# Alarms_and_Buttons.net
KiCad netlist of a schematic drawn in Altium Designer
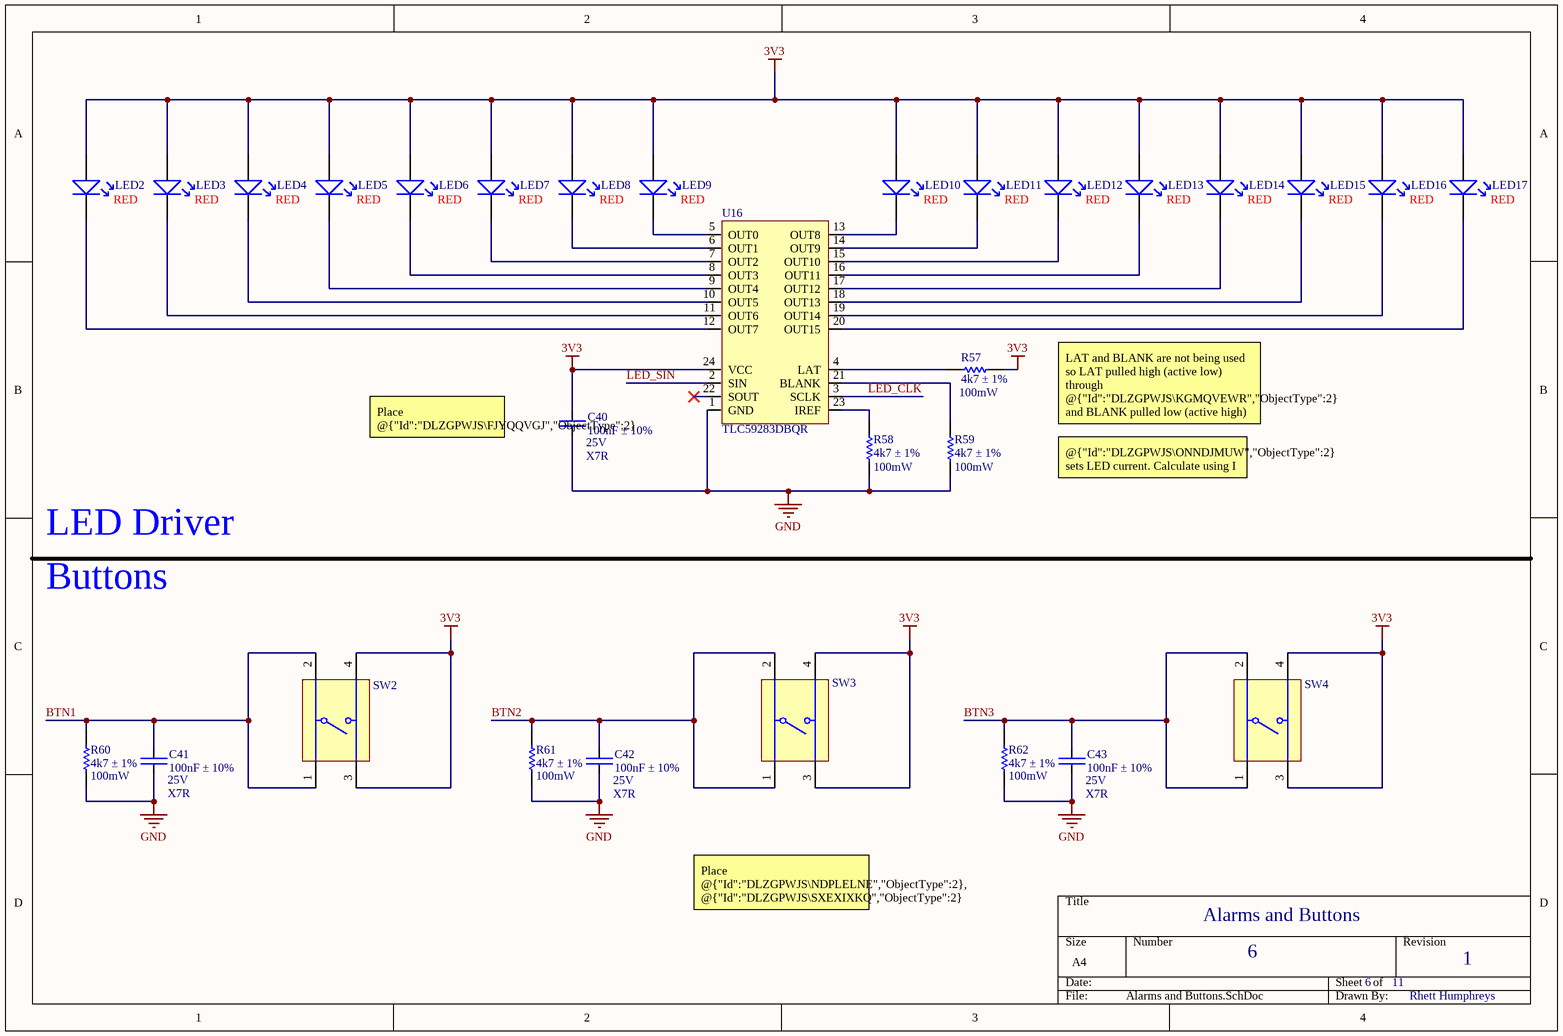
[diagram p0: Alarms and Buttons.SchDoc]

(export (version "E")
  (design (tool "Eeschema 10.0.6"))
  (components
    (comp (ref "C40")
      (value "100nF ± 10%")
      (footprint "CAP-0603")
      (description "Capacitor chip unpolarized. 0603")
      (libsource (lib "Master") (part "CAP-0603"))
    )
    (comp (ref "C41")
      (value "100nF ± 10%")
      (footprint "CAP-0603")
      (description "Capacitor chip unpolarized. 0603")
      (libsource (lib "Master") (part "CAP-0603"))
    )
    (comp (ref "C42")
      (value "100nF ± 10%")
      (footprint "CAP-0603")
      (description "Capacitor chip unpolarized. 0603")
      (libsource (lib "Master") (part "CAP-0603"))
    )
    (comp (ref "C43")
      (value "100nF ± 10%")
      (footprint "CAP-0603")
      (description "Capacitor chip unpolarized. 0603")
      (libsource (lib "Master") (part "CAP-0603"))
    )
    (comp (ref "LED2") (value "~") (footprint "0603 LED") (libsource (lib "Master") (part "0603 LED")))
    (comp (ref "LED3") (value "~") (footprint "0603 LED") (libsource (lib "Master") (part "0603 LED")))
    (comp (ref "LED4") (value "~") (footprint "0603 LED") (libsource (lib "Master") (part "0603 LED")))
    (comp (ref "LED5") (value "~") (footprint "0603 LED") (libsource (lib "Master") (part "0603 LED")))
    (comp (ref "LED6") (value "~") (footprint "0603 LED") (libsource (lib "Master") (part "0603 LED")))
    (comp (ref "LED7") (value "~") (footprint "0603 LED") (libsource (lib "Master") (part "0603 LED")))
    (comp (ref "LED8") (value "~") (footprint "0603 LED") (libsource (lib "Master") (part "0603 LED")))
    (comp (ref "LED9") (value "~") (footprint "0603 LED") (libsource (lib "Master") (part "0603 LED")))
    (comp (ref "LED10") (value "~") (footprint "0603 LED") (libsource (lib "Master") (part "0603 LED")))
    (comp (ref "LED11") (value "~") (footprint "0603 LED") (libsource (lib "Master") (part "0603 LED")))
    (comp (ref "LED12") (value "~") (footprint "0603 LED") (libsource (lib "Master") (part "0603 LED")))
    (comp (ref "LED13") (value "~") (footprint "0603 LED") (libsource (lib "Master") (part "0603 LED")))
    (comp (ref "LED14") (value "~") (footprint "0603 LED") (libsource (lib "Master") (part "0603 LED")))
    (comp (ref "LED15") (value "~") (footprint "0603 LED") (libsource (lib "Master") (part "0603 LED")))
    (comp (ref "LED16") (value "~") (footprint "0603 LED") (libsource (lib "Master") (part "0603 LED")))
    (comp (ref "LED17") (value "~") (footprint "0603 LED") (libsource (lib "Master") (part "0603 LED")))
    (comp (ref "R57")
      (value "4k7 ± 1%")
      (footprint "RES-0603")
      (description "Resistor chip. 0603")
      (libsource (lib "Master") (part "RES-0603"))
    )
    (comp (ref "R58")
      (value "4k7 ± 1%")
      (footprint "RES-0603")
      (description "Resistor chip. 0603")
      (libsource (lib "Master") (part "RES-0603"))
    )
    (comp (ref "R59")
      (value "4k7 ± 1%")
      (footprint "RES-0603")
      (description "Resistor chip. 0603")
      (libsource (lib "Master") (part "RES-0603"))
    )
    (comp (ref "R60")
      (value "4k7 ± 1%")
      (footprint "RES-0603")
      (description "Resistor chip. 0603")
      (libsource (lib "Master") (part "RES-0603"))
    )
    (comp (ref "R61")
      (value "4k7 ± 1%")
      (footprint "RES-0603")
      (description "Resistor chip. 0603")
      (libsource (lib "Master") (part "RES-0603"))
    )
    (comp (ref "R62")
      (value "4k7 ± 1%")
      (footprint "RES-0603")
      (description "Resistor chip. 0603")
      (libsource (lib "Master") (part "RES-0603"))
    )
    (comp (ref "SW2")
      (value "FSM4JSMATR")
      (footprint "TECO-FSM4JSMATR_V")
      (description "Micro Miniature Push Button Switch FSM JSM, 50 mA, -35 to 85 degC, 4-Pin SMD, RoHS, Tape and Reel")
      (fields (field (name "MANUFACTURER") "TE Connectivity"))
      (libsource (lib "Altium Content Vault") (part "SW-SPST-4_A"))
    )
    (comp (ref "SW3")
      (value "FSM4JSMATR")
      (footprint "TECO-FSM4JSMATR_V")
      (description "Micro Miniature Push Button Switch FSM JSM, 50 mA, -35 to 85 degC, 4-Pin SMD, RoHS, Tape and Reel")
      (fields (field (name "MANUFACTURER") "TE Connectivity"))
      (libsource (lib "Altium Content Vault") (part "SW-SPST-4_A"))
    )
    (comp (ref "SW4")
      (value "FSM4JSMATR")
      (footprint "TECO-FSM4JSMATR_V")
      (description "Micro Miniature Push Button Switch FSM JSM, 50 mA, -35 to 85 degC, 4-Pin SMD, RoHS, Tape and Reel")
      (fields (field (name "MANUFACTURER") "TE Connectivity"))
      (libsource (lib "Altium Content Vault") (part "SW-SPST-4_A"))
    )
    (comp (ref "U16")
      (value "TLC59283DBQR")
      (footprint "SOP64P600X175-24N")
      (description "LED Driver Const Current 16 Output")
      (libsource (lib "Master") (part "TLC59283DBQR"))
    )
  )
  (nets
    (net (code "1") (name "/BTN1") (class "Default")
      (node (ref "C41") (pin "2") (pintype "passive"))
      (node (ref "R60") (pin "1") (pintype "passive"))
      (node (ref "SW2") (pin "1") (pinfunction "1_1") (pintype "passive"))
      (node (ref "SW2") (pin "2") (pinfunction "2_2") (pintype "passive"))
    )
    (net (code "2") (name "/BTN2") (class "Default")
      (node (ref "C42") (pin "2") (pintype "passive"))
      (node (ref "R61") (pin "1") (pintype "passive"))
      (node (ref "SW3") (pin "1") (pinfunction "1_1") (pintype "passive"))
      (node (ref "SW3") (pin "2") (pinfunction "2_2") (pintype "passive"))
    )
    (net (code "3") (name "/BTN3") (class "Default")
      (node (ref "C43") (pin "2") (pintype "passive"))
      (node (ref "R62") (pin "1") (pintype "passive"))
      (node (ref "SW4") (pin "1") (pinfunction "1_1") (pintype "passive"))
      (node (ref "SW4") (pin "2") (pinfunction "2_2") (pintype "passive"))
    )
    (net (code "4") (name "/LED_CLK") (class "Default")
      (node (ref "U16") (pin "3") (pinfunction "SCLK_3") (pintype "passive"))
    )
    (net (code "5") (name "/LED_SIN") (class "Default")
      (node (ref "U16") (pin "2") (pinfunction "SIN_2") (pintype "passive"))
    )
    (net (code "6") (name "3V3") (class "Default")
      (node (ref "C40") (pin "2") (pintype "passive"))
      (node (ref "LED10") (pin "1") (pinfunction "6_1") (pintype "passive"))
      (node (ref "LED11") (pin "1") (pinfunction "6_1") (pintype "passive"))
      (node (ref "LED12") (pin "1") (pinfunction "6_1") (pintype "passive"))
      (node (ref "LED13") (pin "1") (pinfunction "6_1") (pintype "passive"))
      (node (ref "LED14") (pin "1") (pinfunction "6_1") (pintype "passive"))
      (node (ref "LED15") (pin "1") (pinfunction "6_1") (pintype "passive"))
      (node (ref "LED16") (pin "1") (pinfunction "6_1") (pintype "passive"))
      (node (ref "LED17") (pin "1") (pinfunction "6_1") (pintype "passive"))
      (node (ref "LED2") (pin "1") (pinfunction "6_1") (pintype "passive"))
      (node (ref "LED3") (pin "1") (pinfunction "6_1") (pintype "passive"))
      (node (ref "LED4") (pin "1") (pinfunction "6_1") (pintype "passive"))
      (node (ref "LED5") (pin "1") (pinfunction "6_1") (pintype "passive"))
      (node (ref "LED6") (pin "1") (pinfunction "6_1") (pintype "passive"))
      (node (ref "LED7") (pin "1") (pinfunction "6_1") (pintype "passive"))
      (node (ref "LED8") (pin "1") (pinfunction "6_1") (pintype "passive"))
      (node (ref "LED9") (pin "1") (pinfunction "6_1") (pintype "passive"))
      (node (ref "R57") (pin "2") (pintype "passive"))
      (node (ref "SW2") (pin "3") (pinfunction "3_3") (pintype "passive"))
      (node (ref "SW2") (pin "4") (pinfunction "4_4") (pintype "passive"))
      (node (ref "SW3") (pin "3") (pinfunction "3_3") (pintype "passive"))
      (node (ref "SW3") (pin "4") (pinfunction "4_4") (pintype "passive"))
      (node (ref "SW4") (pin "3") (pinfunction "3_3") (pintype "passive"))
      (node (ref "SW4") (pin "4") (pinfunction "4_4") (pintype "passive"))
      (node (ref "U16") (pin "24") (pinfunction "VCC_24") (pintype "passive"))
    )
    (net (code "7") (name "GND") (class "Default")
      (node (ref "C40") (pin "1") (pintype "passive"))
      (node (ref "C41") (pin "1") (pintype "passive"))
      (node (ref "C42") (pin "1") (pintype "passive"))
      (node (ref "C43") (pin "1") (pintype "passive"))
      (node (ref "R58") (pin "1") (pintype "passive"))
      (node (ref "R59") (pin "1") (pintype "passive"))
      (node (ref "R60") (pin "2") (pintype "passive"))
      (node (ref "R61") (pin "2") (pintype "passive"))
      (node (ref "R62") (pin "2") (pintype "passive"))
      (node (ref "U16") (pin "1") (pinfunction "GND_1") (pintype "passive"))
    )
    (net (code "8") (name "Net-(LED2-5)") (class "Default")
      (node (ref "LED2") (pin "2") (pinfunction "5_2") (pintype "passive"))
      (node (ref "U16") (pin "12") (pinfunction "OUT7_12") (pintype "passive"))
    )
    (net (code "9") (name "Net-(LED3-5)") (class "Default")
      (node (ref "LED3") (pin "2") (pinfunction "5_2") (pintype "passive"))
      (node (ref "U16") (pin "11") (pinfunction "OUT6_11") (pintype "passive"))
    )
    (net (code "10") (name "Net-(LED4-5)") (class "Default")
      (node (ref "LED4") (pin "2") (pinfunction "5_2") (pintype "passive"))
      (node (ref "U16") (pin "10") (pinfunction "OUT5_10") (pintype "passive"))
    )
    (net (code "11") (name "Net-(LED5-5)") (class "Default")
      (node (ref "LED5") (pin "2") (pinfunction "5_2") (pintype "passive"))
      (node (ref "U16") (pin "9") (pinfunction "OUT4_9") (pintype "passive"))
    )
    (net (code "12") (name "Net-(LED6-5)") (class "Default")
      (node (ref "LED6") (pin "2") (pinfunction "5_2") (pintype "passive"))
      (node (ref "U16") (pin "8") (pinfunction "OUT3_8") (pintype "passive"))
    )
    (net (code "13") (name "Net-(LED7-5)") (class "Default")
      (node (ref "LED7") (pin "2") (pinfunction "5_2") (pintype "passive"))
      (node (ref "U16") (pin "7") (pinfunction "OUT2_7") (pintype "passive"))
    )
    (net (code "14") (name "Net-(LED8-5)") (class "Default")
      (node (ref "LED8") (pin "2") (pinfunction "5_2") (pintype "passive"))
      (node (ref "U16") (pin "6") (pinfunction "OUT1_6") (pintype "passive"))
    )
    (net (code "15") (name "Net-(LED9-5)") (class "Default")
      (node (ref "LED9") (pin "2") (pinfunction "5_2") (pintype "passive"))
      (node (ref "U16") (pin "5") (pinfunction "OUT0_5") (pintype "passive"))
    )
    (net (code "16") (name "Net-(LED10-5)") (class "Default")
      (node (ref "LED10") (pin "2") (pinfunction "5_2") (pintype "passive"))
      (node (ref "U16") (pin "13") (pinfunction "OUT8_13") (pintype "passive"))
    )
    (net (code "17") (name "Net-(LED11-5)") (class "Default")
      (node (ref "LED11") (pin "2") (pinfunction "5_2") (pintype "passive"))
      (node (ref "U16") (pin "14") (pinfunction "OUT9_14") (pintype "passive"))
    )
    (net (code "18") (name "Net-(LED12-5)") (class "Default")
      (node (ref "LED12") (pin "2") (pinfunction "5_2") (pintype "passive"))
      (node (ref "U16") (pin "15") (pinfunction "OUT10_15") (pintype "passive"))
    )
    (net (code "19") (name "Net-(LED13-5)") (class "Default")
      (node (ref "LED13") (pin "2") (pinfunction "5_2") (pintype "passive"))
      (node (ref "U16") (pin "16") (pinfunction "OUT11_16") (pintype "passive"))
    )
    (net (code "20") (name "Net-(LED14-5)") (class "Default")
      (node (ref "LED14") (pin "2") (pinfunction "5_2") (pintype "passive"))
      (node (ref "U16") (pin "17") (pinfunction "OUT12_17") (pintype "passive"))
    )
    (net (code "21") (name "Net-(LED15-5)") (class "Default")
      (node (ref "LED15") (pin "2") (pinfunction "5_2") (pintype "passive"))
      (node (ref "U16") (pin "18") (pinfunction "OUT13_18") (pintype "passive"))
    )
    (net (code "22") (name "Net-(LED16-5)") (class "Default")
      (node (ref "LED16") (pin "2") (pinfunction "5_2") (pintype "passive"))
      (node (ref "U16") (pin "19") (pinfunction "OUT14_19") (pintype "passive"))
    )
    (net (code "23") (name "Net-(LED17-5)") (class "Default")
      (node (ref "LED17") (pin "2") (pinfunction "5_2") (pintype "passive"))
      (node (ref "U16") (pin "20") (pinfunction "OUT15_20") (pintype "passive"))
    )
    (net (code "24") (name "Net-(U16-BLANK)") (class "Default")
      (node (ref "R59") (pin "2") (pintype "passive"))
      (node (ref "U16") (pin "21") (pinfunction "BLANK_21") (pintype "passive"))
    )
    (net (code "25") (name "Net-(U16-IREF)") (class "Default")
      (node (ref "R58") (pin "2") (pintype "passive"))
      (node (ref "U16") (pin "23") (pinfunction "IREF_23") (pintype "passive"))
    )
    (net (code "26") (name "Net-(U16-LAT)") (class "Default")
      (node (ref "R57") (pin "1") (pintype "passive"))
      (node (ref "U16") (pin "4") (pinfunction "LAT_4") (pintype "passive"))
    )
    (net (code "27") (name "unconnected-(U16-SOUT-Pad22)") (class "Default")
      (node (ref "U16") (pin "22") (pinfunction "SOUT_22") (pintype "passive+no_connect"))
    )
  )
)
